# usb_hub.net
KiCad netlist of a schematic drawn in Altium Designer
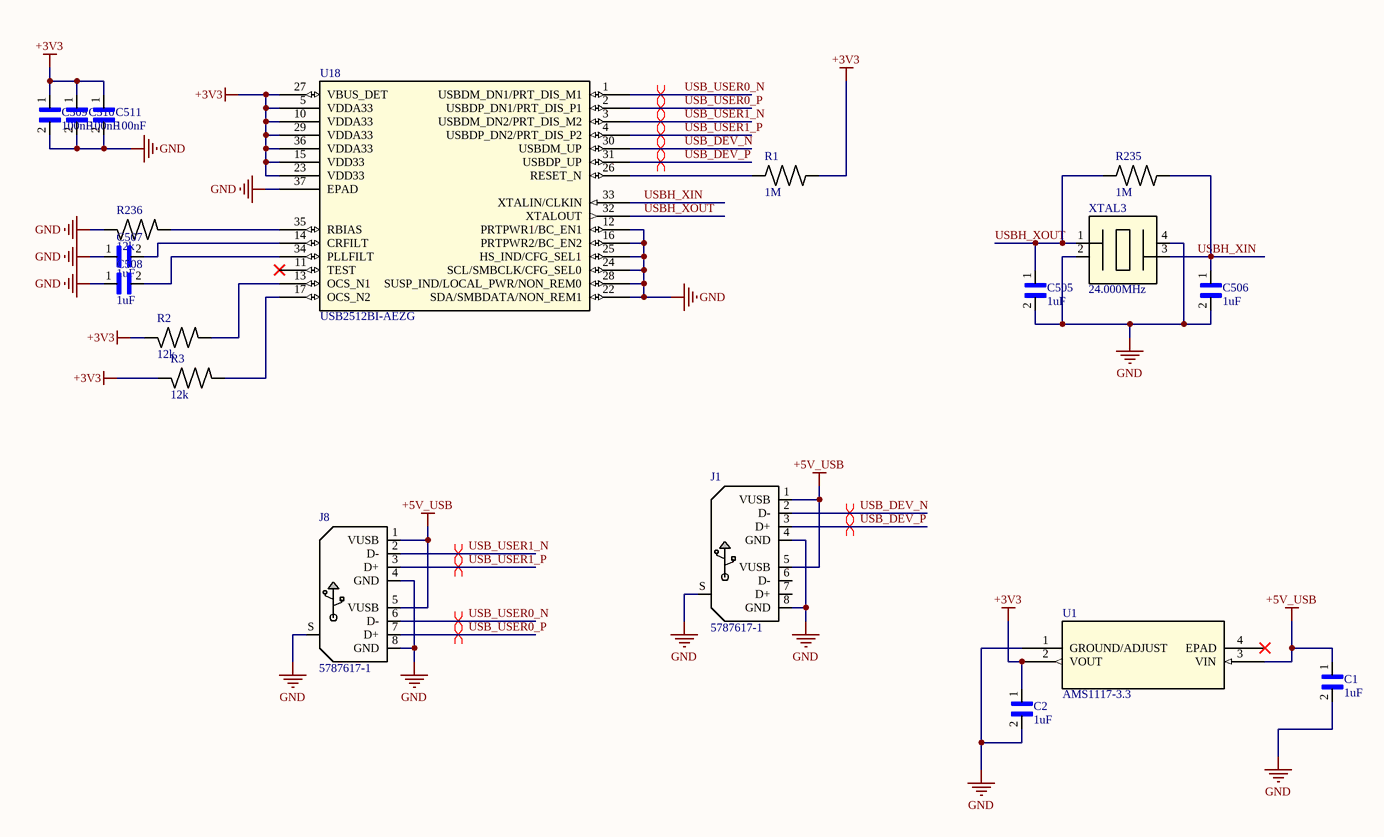
[diagram p0: usb_hub.SchDoc]

(export (version "E")
  (design (tool "Eeschema 10.0.6"))
  (components
    (comp (ref "C1")
      (value "1uF")
      (footprint "*CAPC1608X90N")
      (description "0603 10 nF 25 V 10% Tolerance X7R Surface Mount Multilayer Ceramic Capacitor")
      (fields (field (name "MP") "06033C103KAT2A") (field (name "MF") "AVX"))
      (libsource (lib "06033C103KAT2A") (part "06033C103KAT2A"))
    )
    (comp (ref "C2")
      (value "1uF")
      (footprint "*CAPC1608X90N")
      (description "0603 10 nF 25 V 10% Tolerance X7R Surface Mount Multilayer Ceramic Capacitor")
      (fields (field (name "MP") "06033C103KAT2A") (field (name "MF") "AVX"))
      (libsource (lib "06033C103KAT2A") (part "06033C103KAT2A"))
    )
    (comp (ref "C505")
      (value "1uF")
      (footprint "*CAPC1608X90N")
      (description "0603 10 nF 25 V 10% Tolerance X7R Surface Mount Multilayer Ceramic Capacitor")
      (fields (field (name "MP") "06033C103KAT2A") (field (name "MF") "AVX"))
      (libsource (lib "06033C103KAT2A") (part "06033C103KAT2A"))
    )
    (comp (ref "C506")
      (value "1uF")
      (footprint "*CAPC1608X90N")
      (description "0603 10 nF 25 V 10% Tolerance X7R Surface Mount Multilayer Ceramic Capacitor")
      (fields (field (name "MP") "06033C103KAT2A") (field (name "MF") "AVX"))
      (libsource (lib "06033C103KAT2A") (part "06033C103KAT2A"))
    )
    (comp (ref "C507")
      (value "1uF")
      (footprint "*CAPC1608X90N")
      (description "0603 10 nF 25 V 10% Tolerance X7R Surface Mount Multilayer Ceramic Capacitor")
      (fields (field (name "MP") "06033C103KAT2A") (field (name "MF") "AVX"))
      (libsource (lib "06033C103KAT2A") (part "06033C103KAT2A"))
    )
    (comp (ref "C508")
      (value "1uF")
      (footprint "*CAPC1608X90N")
      (description "0603 10 nF 25 V 10% Tolerance X7R Surface Mount Multilayer Ceramic Capacitor")
      (fields (field (name "MP") "06033C103KAT2A") (field (name "MF") "AVX"))
      (libsource (lib "06033C103KAT2A") (part "06033C103KAT2A"))
    )
    (comp (ref "C509")
      (value "100nF")
      (footprint "*CAPC1608X90N")
      (description "0603 10 nF 25 V 10% Tolerance X7R Surface Mount Multilayer Ceramic Capacitor")
      (fields (field (name "MP") "06033C103KAT2A") (field (name "MF") "AVX"))
      (libsource (lib "06033C103KAT2A") (part "06033C103KAT2A"))
    )
    (comp (ref "C510")
      (value "100nF")
      (footprint "*CAPC1608X90N")
      (description "0603 10 nF 25 V 10% Tolerance X7R Surface Mount Multilayer Ceramic Capacitor")
      (fields (field (name "MP") "06033C103KAT2A") (field (name "MF") "AVX"))
      (libsource (lib "06033C103KAT2A") (part "06033C103KAT2A"))
    )
    (comp (ref "C511")
      (value "100nF")
      (footprint "*CAPC1608X90N")
      (description "0603 10 nF 25 V 10% Tolerance X7R Surface Mount Multilayer Ceramic Capacitor")
      (fields (field (name "MP") "06033C103KAT2A") (field (name "MF") "AVX"))
      (libsource (lib "06033C103KAT2A") (part "06033C103KAT2A"))
    )
    (comp (ref "J1")
      (value "5787617-1")
      (footprint "CONN8_5787617-1_TEC")
      (description "RECP ASSY, R/A, STACKED, THRU-HOLE, USB,")
      (fields (field (name "COPYRIGHT") "Copyright (C) 2016 Accelerated Designs. All rights reserved"))
      (libsource (lib "57876171") (part "5787617-1"))
    )
    (comp (ref "J8")
      (value "5787617-1")
      (footprint "CONN8_5787617-1_TEC")
      (description "RECP ASSY, R/A, STACKED, THRU-HOLE, USB,")
      (fields (field (name "COPYRIGHT") "Copyright (C) 2016 Accelerated Designs. All rights reserved"))
      (libsource (lib "57876171") (part "5787617-1"))
    )
    (comp (ref "R1")
      (value "1M")
      (footprint "*RESC1608X55N")
      (description "Res Thick Film 0603 4.7K Ohm 1% 1/10W 100ppm/C Molded SMD SMD Paper Tape on Plastic Reel")
      (fields (field (name "MP") "CR0603-FX-4701ELF") (field (name "MF") "Bourns"))
      (libsource (lib "CR0603-FX-4701ELF") (part "CR0603-FX-4701ELF"))
    )
    (comp (ref "R2")
      (value "12k")
      (footprint "*RESC1608X55N")
      (description "Res Thick Film 0603 4.7K Ohm 1% 1/10W 100ppm/C Molded SMD SMD Paper Tape on Plastic Reel")
      (fields (field (name "MP") "CR0603-FX-4701ELF") (field (name "MF") "Bourns"))
      (libsource (lib "CR0603-FX-4701ELF") (part "CR0603-FX-4701ELF"))
    )
    (comp (ref "R3")
      (value "12k")
      (footprint "*RESC1608X55N")
      (description "Res Thick Film 0603 4.7K Ohm 1% 1/10W 100ppm/C Molded SMD SMD Paper Tape on Plastic Reel")
      (fields (field (name "MP") "CR0603-FX-4701ELF") (field (name "MF") "Bourns"))
      (libsource (lib "CR0603-FX-4701ELF") (part "CR0603-FX-4701ELF"))
    )
    (comp (ref "R235")
      (value "1M")
      (footprint "*RESC1608X55N")
      (description "Res Thick Film 0603 4.7K Ohm 1% 1/10W 100ppm/C Molded SMD SMD Paper Tape on Plastic Reel")
      (fields (field (name "MP") "CR0603-FX-4701ELF") (field (name "MF") "Bourns"))
      (libsource (lib "CR0603-FX-4701ELF") (part "CR0603-FX-4701ELF"))
    )
    (comp (ref "R236")
      (value "12k")
      (footprint "*RESC1608X55N")
      (description "Res Thick Film 0603 4.7K Ohm 1% 1/10W 100ppm/C Molded SMD SMD Paper Tape on Plastic Reel")
      (fields (field (name "MP") "CR0603-FX-4701ELF") (field (name "MF") "Bourns"))
      (libsource (lib "CR0603-FX-4701ELF") (part "CR0603-FX-4701ELF"))
    )
    (comp (ref "U1")
      (value "AMS1117-3.3")
      (footprint "SOT_AMS_ADS")
      (description "No Description Available")
      (fields (field (name "COPYRIGHT") "Copyright (C) 2018 Accelerated Designs. All rights reserved"))
      (libsource (lib "AMS111733") (part "AMS1117-3.3"))
    )
    (comp (ref "U18")
      (value "USB2512BI-AEZG")
      (footprint "QFN36_6X6MC_MCH")
      (description "No Description Available")
      (fields (field (name "COPYRIGHT") "Copyright (C) 2018 Accelerated Designs. All rights reserved"))
      (libsource (lib "USB2512BIAEZG") (part "USB2512BI-AEZG"))
    )
    (comp (ref "XTAL3")
      (value "24.000MHz")
      (footprint "SMD-4_2P5X2_AVX")
      (description "No Description Available")
      (fields
        (field (name "MANUFACTURER_PART_NUMBER") "CX2520DB25000H0FLJC1")
        (field (name "COPYRIGHT") "Copyright (C) 2018 Accelerated Designs. All rights reserved")
      )
      (libsource (lib "2020-11-11_05-03-17") (part "CX2520DB25000H0FLJC1"))
    )
  )
  (nets
    (net (code "1") (name "+3V3") (class "Default")
      (node (ref "C2") (pin "1") (pinfunction "1_1") (pintype "passive"))
      (node (ref "C509") (pin "1") (pinfunction "1_1") (pintype "passive"))
      (node (ref "C510") (pin "1") (pinfunction "1_1") (pintype "passive"))
      (node (ref "C511") (pin "1") (pinfunction "1_1") (pintype "passive"))
      (node (ref "R1") (pin "2") (pinfunction "2_2") (pintype "passive"))
      (node (ref "R2") (pin "1") (pinfunction "1_1") (pintype "passive"))
      (node (ref "R3") (pin "1") (pinfunction "1_1") (pintype "passive"))
      (node (ref "U1") (pin "2") (pinfunction "VOUT_2") (pintype "output"))
      (node (ref "U18") (pin "10") (pinfunction "VDDA33_10") (pintype "power_in"))
      (node (ref "U18") (pin "15") (pinfunction "VDD33_15") (pintype "power_in"))
      (node (ref "U18") (pin "23") (pinfunction "VDD33_23") (pintype "power_in"))
      (node (ref "U18") (pin "27") (pinfunction "VBUS_DET_27") (pintype "bidirectional"))
      (node (ref "U18") (pin "29") (pinfunction "VDDA33_29") (pintype "power_in"))
      (node (ref "U18") (pin "36") (pinfunction "VDDA33_36") (pintype "power_in"))
      (node (ref "U18") (pin "5") (pinfunction "VDDA33_5") (pintype "power_in"))
    )
    (net (code "2") (name "+5V_USB") (class "Default")
      (node (ref "C1") (pin "1") (pinfunction "1_1") (pintype "passive"))
      (node (ref "J1") (pin "1") (pinfunction "VUSB_1") (pintype "passive"))
      (node (ref "J1") (pin "5") (pinfunction "VUSB_5") (pintype "passive"))
      (node (ref "J8") (pin "1") (pinfunction "VUSB_1") (pintype "passive"))
      (node (ref "J8") (pin "5") (pinfunction "VUSB_5") (pintype "passive"))
      (node (ref "U1") (pin "3") (pinfunction "VIN_3") (pintype "input"))
    )
    (net (code "3") (name "/USBH_XIN") (class "Default")
      (node (ref "C506") (pin "1") (pinfunction "1_1") (pintype "passive"))
      (node (ref "R235") (pin "2") (pinfunction "2_2") (pintype "passive"))
      (node (ref "U18") (pin "33") (pinfunction "XTALIN/CLKIN_33") (pintype "input"))
      (node (ref "XTAL3") (pin "3") (pinfunction "HOT_3") (pintype "passive"))
    )
    (net (code "4") (name "/USBH_XOUT") (class "Default")
      (node (ref "C505") (pin "1") (pinfunction "1_1") (pintype "passive"))
      (node (ref "R235") (pin "1") (pinfunction "1_1") (pintype "passive"))
      (node (ref "U18") (pin "32") (pinfunction "XTALOUT_32") (pintype "output"))
      (node (ref "XTAL3") (pin "1") (pinfunction "HOT_1") (pintype "passive"))
    )
    (net (code "5") (name "/USB_DEV_N") (class "Default")
      (node (ref "J1") (pin "2") (pinfunction "D-_2") (pintype "passive"))
      (node (ref "U18") (pin "30") (pinfunction "USBDM_UP_30") (pintype "bidirectional"))
    )
    (net (code "6") (name "/USB_DEV_P") (class "Default")
      (node (ref "J1") (pin "3") (pinfunction "D+_3") (pintype "passive"))
      (node (ref "U18") (pin "31") (pinfunction "USBDP_UP_31") (pintype "bidirectional"))
    )
    (net (code "7") (name "/USB_USER0_N") (class "Default")
      (node (ref "J8") (pin "6") (pinfunction "D-_6") (pintype "passive"))
      (node (ref "U18") (pin "1") (pinfunction "USBDM_DN1/PRT_DIS_M1_1") (pintype "bidirectional"))
    )
    (net (code "8") (name "/USB_USER0_P") (class "Default")
      (node (ref "J8") (pin "7") (pinfunction "D+_7") (pintype "passive"))
      (node (ref "U18") (pin "2") (pinfunction "USBDP_DN1/PRT_DIS_P1_2") (pintype "bidirectional"))
    )
    (net (code "9") (name "/USB_USER1_N") (class "Default")
      (node (ref "J8") (pin "2") (pinfunction "D-_2") (pintype "passive"))
      (node (ref "U18") (pin "3") (pinfunction "USBDM_DN2/PRT_DIS_M2_3") (pintype "bidirectional"))
    )
    (net (code "10") (name "/USB_USER1_P") (class "Default")
      (node (ref "J8") (pin "3") (pinfunction "D+_3") (pintype "passive"))
      (node (ref "U18") (pin "4") (pinfunction "USBDP_DN2/PRT_DIS_P2_4") (pintype "bidirectional"))
    )
    (net (code "11") (name "GND") (class "Default")
      (node (ref "C1") (pin "2") (pinfunction "2_2") (pintype "passive"))
      (node (ref "C2") (pin "2") (pinfunction "2_2") (pintype "passive"))
      (node (ref "C505") (pin "2") (pinfunction "2_2") (pintype "passive"))
      (node (ref "C506") (pin "2") (pinfunction "2_2") (pintype "passive"))
      (node (ref "C507") (pin "1") (pinfunction "1_1") (pintype "passive"))
      (node (ref "C508") (pin "1") (pinfunction "1_1") (pintype "passive"))
      (node (ref "C509") (pin "2") (pinfunction "2_2") (pintype "passive"))
      (node (ref "C510") (pin "2") (pinfunction "2_2") (pintype "passive"))
      (node (ref "C511") (pin "2") (pinfunction "2_2") (pintype "passive"))
      (node (ref "J1") (pin "4") (pinfunction "GND_4") (pintype "passive"))
      (node (ref "J1") (pin "8") (pinfunction "GND_8") (pintype "passive"))
      (node (ref "J1") (pin "S") (pinfunction "S_S") (pintype "passive"))
      (node (ref "J8") (pin "4") (pinfunction "GND_4") (pintype "passive"))
      (node (ref "J8") (pin "8") (pinfunction "GND_8") (pintype "passive"))
      (node (ref "J8") (pin "S") (pinfunction "S_S") (pintype "passive"))
      (node (ref "R236") (pin "1") (pinfunction "1_1") (pintype "passive"))
      (node (ref "U1") (pin "1") (pinfunction "GROUND/ADJUST_1") (pintype "passive"))
      (node (ref "U18") (pin "12") (pinfunction "PRTPWR1/BC_EN1_12") (pintype "bidirectional"))
      (node (ref "U18") (pin "16") (pinfunction "PRTPWR2/BC_EN2_16") (pintype "bidirectional"))
      (node (ref "U18") (pin "22") (pinfunction "SDA/SMBDATA/NON_REM1_22") (pintype "bidirectional"))
      (node (ref "U18") (pin "24") (pinfunction "SCL/SMBCLK/CFG_SEL0_24") (pintype "bidirectional"))
      (node (ref "U18") (pin "25") (pinfunction "HS_IND/CFG_SEL1_25") (pintype "bidirectional"))
      (node (ref "U18") (pin "28") (pinfunction "SUSP_IND/LOCAL_PWR/NON_REM0_28") (pintype "bidirectional"))
      (node (ref "U18") (pin "37") (pinfunction "EPAD_37") (pintype "passive"))
      (node (ref "XTAL3") (pin "2") (pinfunction "GND_2") (pintype "passive"))
      (node (ref "XTAL3") (pin "4") (pinfunction "GND(NC)_4") (pintype "passive"))
    )
    (net (code "12") (name "Net-(U18-CRFILT)") (class "Default")
      (node (ref "C507") (pin "2") (pinfunction "2_2") (pintype "passive"))
      (node (ref "U18") (pin "14") (pinfunction "CRFILT_14") (pintype "bidirectional"))
    )
    (net (code "13") (name "Net-(U18-OCS_N1)") (class "Default")
      (node (ref "R2") (pin "2") (pinfunction "2_2") (pintype "passive"))
      (node (ref "U18") (pin "13") (pinfunction "OCS_N1_13") (pintype "bidirectional"))
    )
    (net (code "14") (name "Net-(U18-OCS_N2)") (class "Default")
      (node (ref "R3") (pin "2") (pinfunction "2_2") (pintype "passive"))
      (node (ref "U18") (pin "17") (pinfunction "OCS_N2_17") (pintype "bidirectional"))
    )
    (net (code "15") (name "Net-(U18-PLLFILT)") (class "Default")
      (node (ref "C508") (pin "2") (pinfunction "2_2") (pintype "passive"))
      (node (ref "U18") (pin "34") (pinfunction "PLLFILT_34") (pintype "bidirectional"))
    )
    (net (code "16") (name "Net-(U18-RBIAS)") (class "Default")
      (node (ref "R236") (pin "2") (pinfunction "2_2") (pintype "passive"))
      (node (ref "U18") (pin "35") (pinfunction "RBIAS_35") (pintype "bidirectional"))
    )
    (net (code "17") (name "Net-(U18-RESET_N)") (class "Default")
      (node (ref "R1") (pin "1") (pinfunction "1_1") (pintype "passive"))
      (node (ref "U18") (pin "26") (pinfunction "RESET_N_26") (pintype "bidirectional"))
    )
    (net (code "18") (name "unconnected-(J1-D+-Pad7)") (class "Default")
      (node (ref "J1") (pin "7") (pinfunction "D+_7") (pintype "passive"))
    )
    (net (code "19") (name "unconnected-(J1-D--Pad6)") (class "Default")
      (node (ref "J1") (pin "6") (pinfunction "D-_6") (pintype "passive"))
    )
    (net (code "20") (name "unconnected-(U1-EPAD-Pad4)") (class "Default")
      (node (ref "U1") (pin "4") (pinfunction "EPAD_4") (pintype "power_in+no_connect"))
    )
    (net (code "21") (name "unconnected-(U18-TEST-Pad11)") (class "Default")
      (node (ref "U18") (pin "11") (pinfunction "TEST_11") (pintype "bidirectional+no_connect"))
    )
  )
)
